# driver2REV1.net
KiCad netlist of a schematic drawn in EAGLE
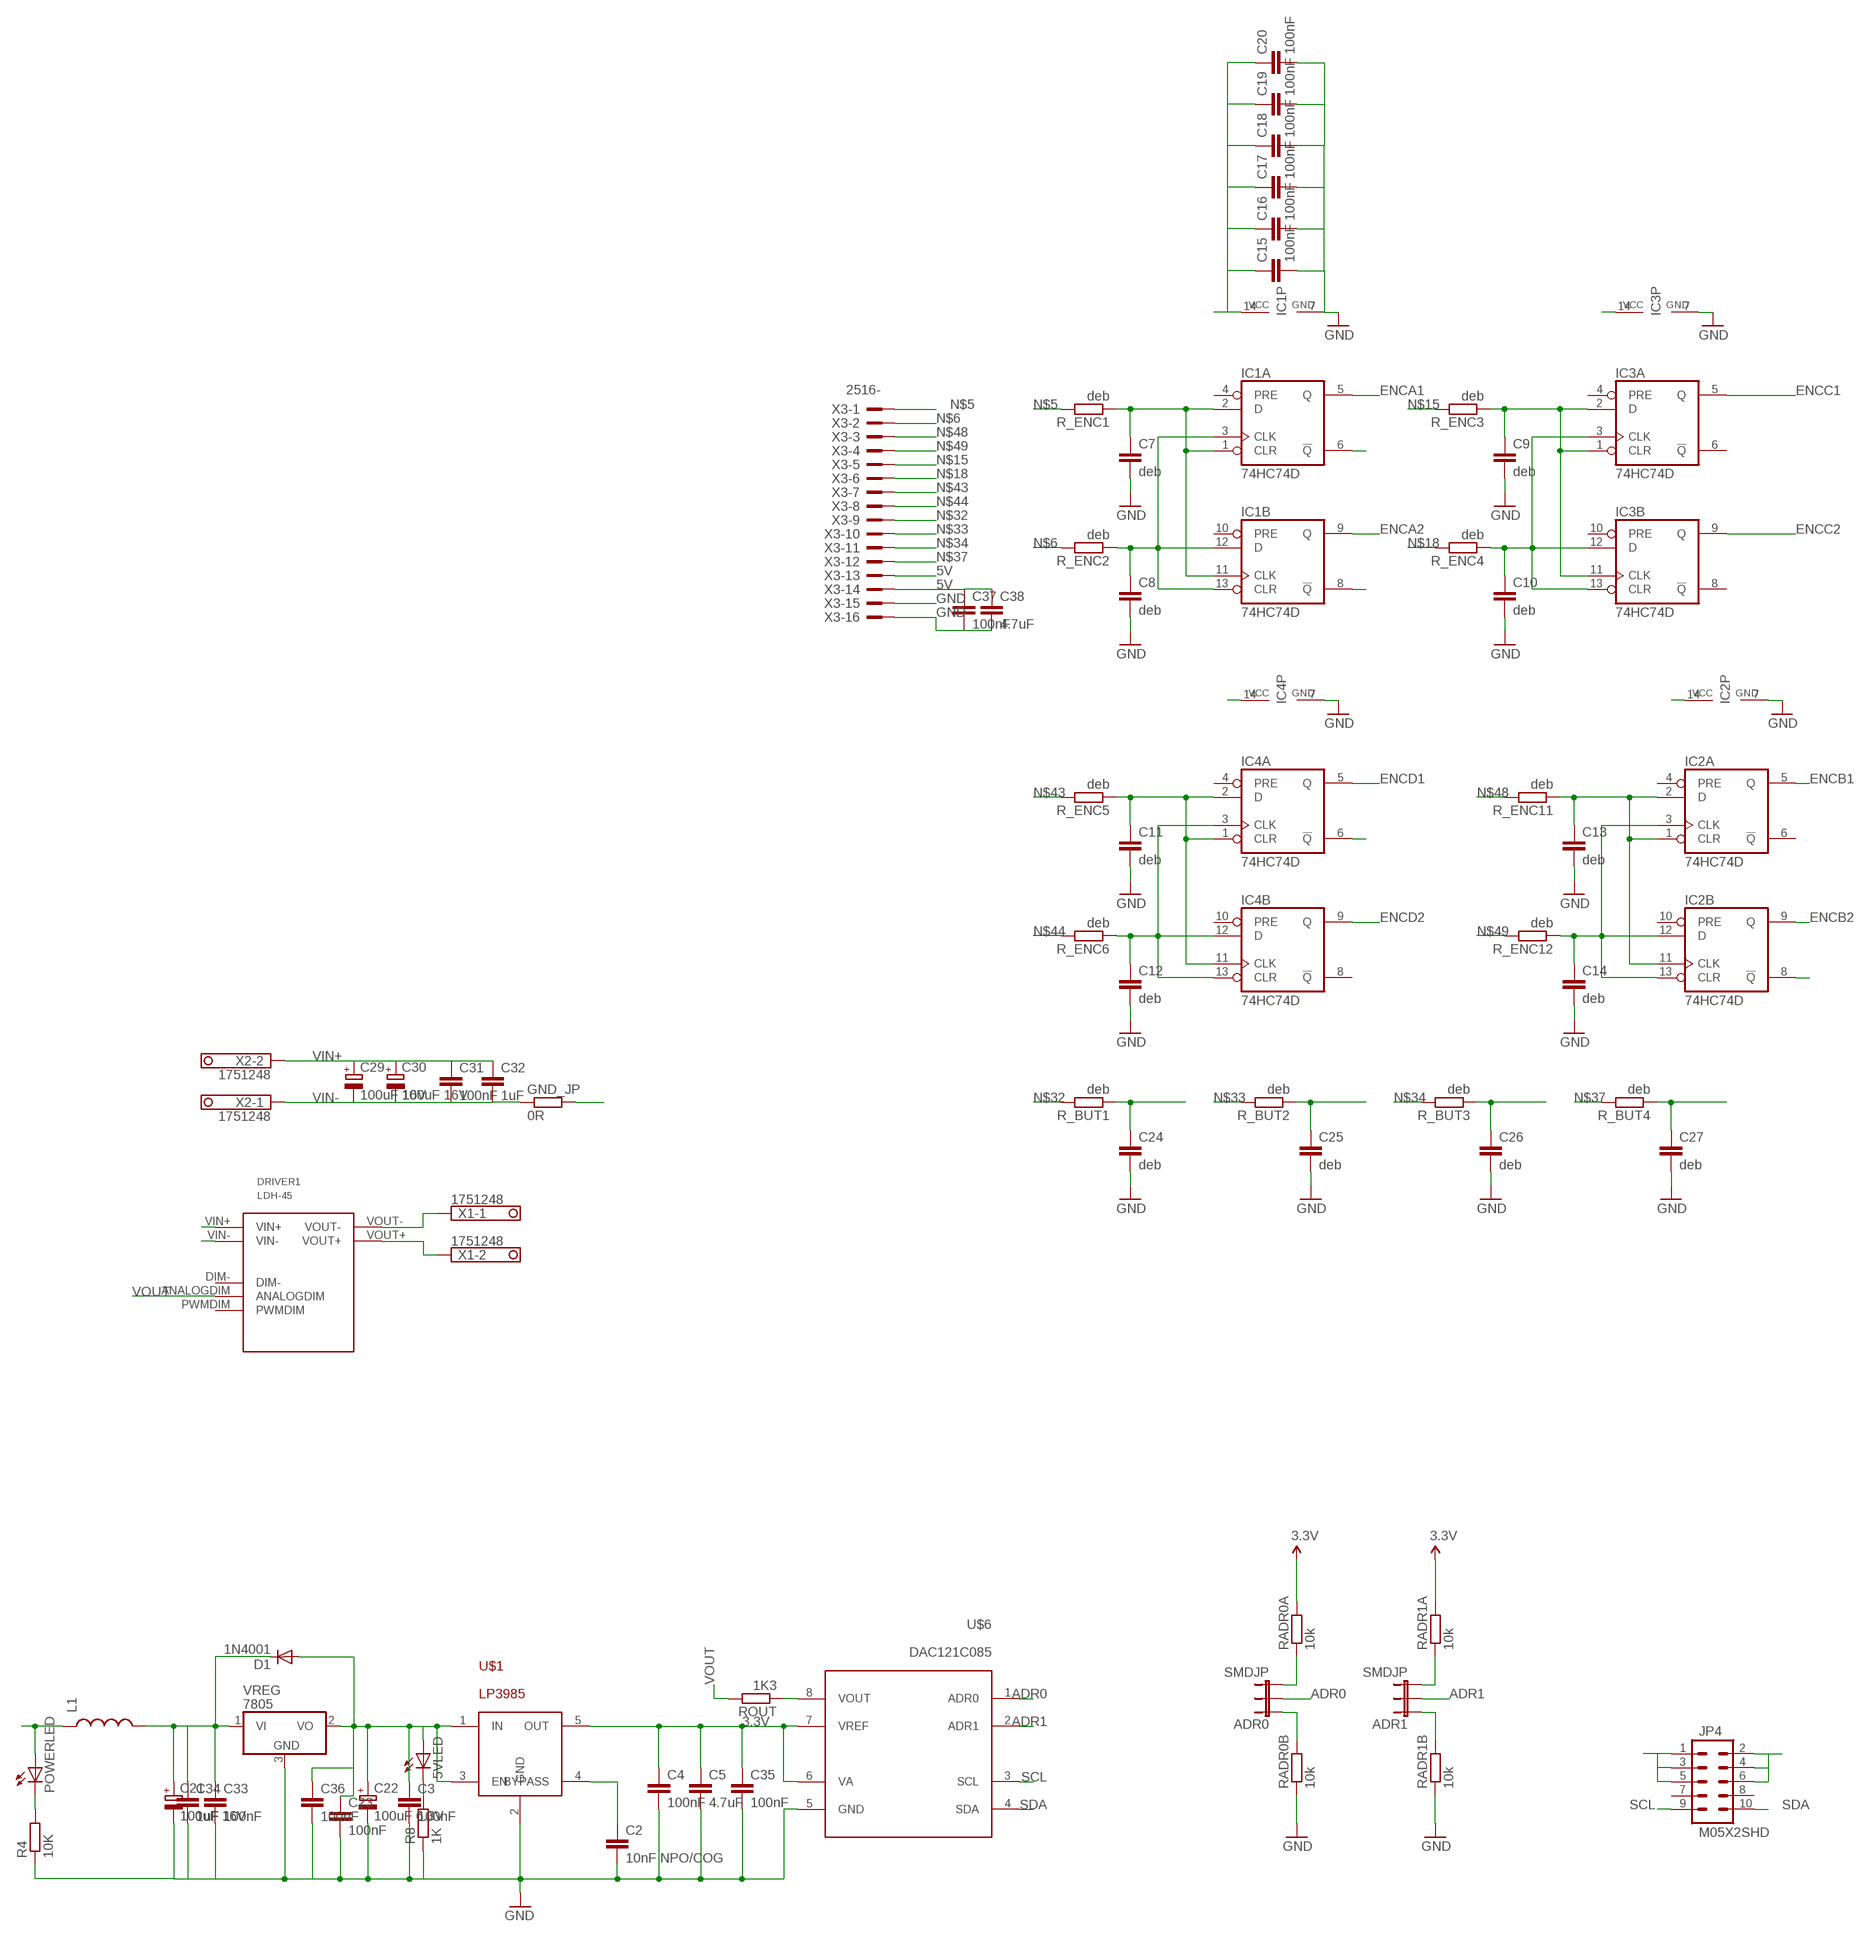
[diagram p0: schematic, sheet 1]
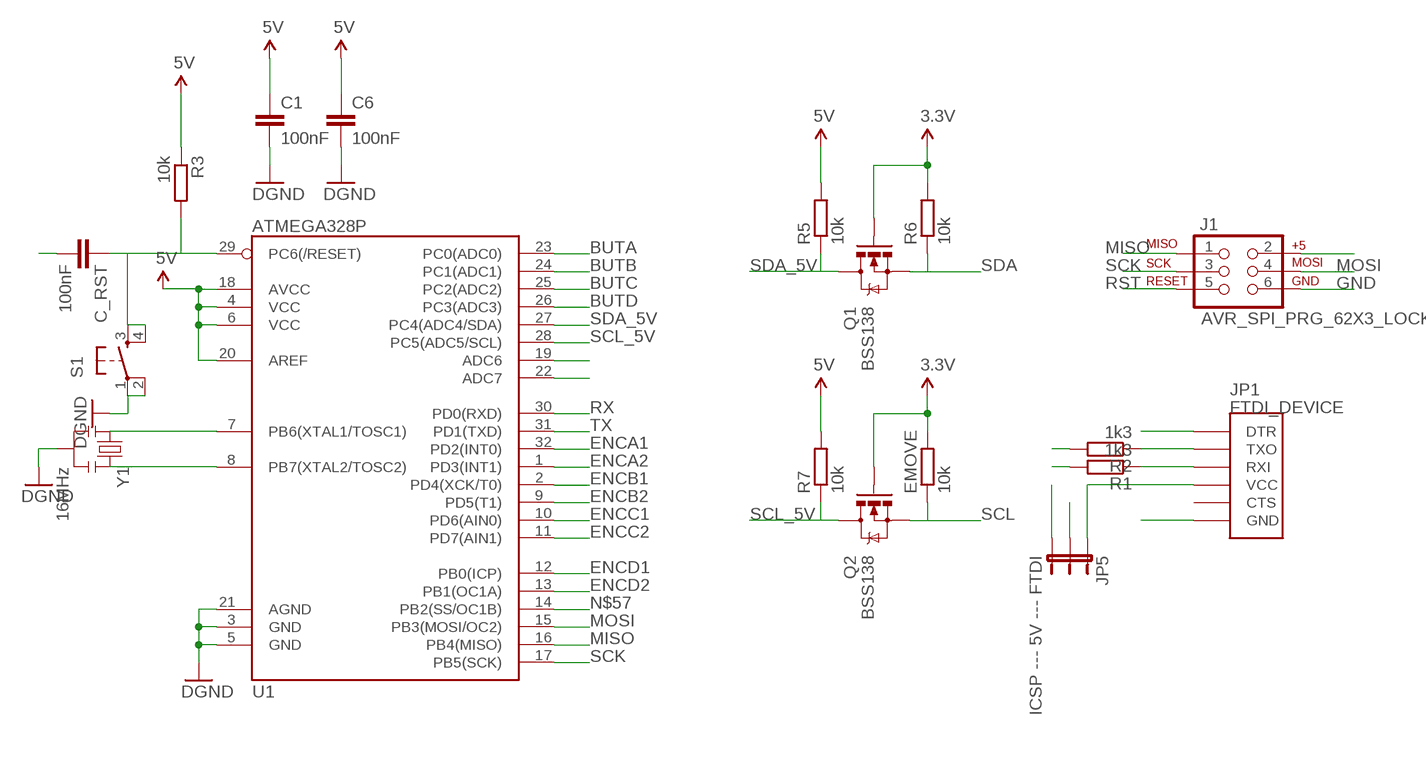
[diagram p1: schematic, sheet 2]

(export (version "E")
  (design (tool "Eeschema 10.0.6"))
  (components
    (comp (ref "5VLED")
      (value "LEDCHIP-LED0805")
      (footprint "eagle-import:CHIP-LED0805")
      (libsource (lib "eagle-import") (part "LEDCHIP-LED0805"))
    )
    (comp (ref "ADR0")
      (value "SMDJP")
      (footprint "eagle-import:SJ_3")
      (libsource (lib "eagle-import") (part "JUMPER-3-OLDSMD"))
    )
    (comp (ref "ADR1")
      (value "SMDJP")
      (footprint "eagle-import:SJ_3")
      (libsource (lib "eagle-import") (part "JUMPER-3-OLDSMD"))
    )
    (comp (ref "C2")
      (value "10nF NPO/COG")
      (footprint "eagle-import:C0805")
      (libsource (lib "eagle-import") (part "C-EUC0805"))
    )
    (comp (ref "C3")
      (value "100nF")
      (footprint "eagle-import:C0805")
      (libsource (lib "eagle-import") (part "C-EUC0805"))
    )
    (comp (ref "C4")
      (value "100nF")
      (footprint "eagle-import:C0805")
      (libsource (lib "eagle-import") (part "C-EUC0805"))
    )
    (comp (ref "C5")
      (value "4.7uF")
      (footprint "eagle-import:C0805")
      (libsource (lib "eagle-import") (part "C-EUC0805"))
    )
    (comp (ref "C7")
      (value "deb")
      (footprint "eagle-import:C0805")
      (libsource (lib "eagle-import") (part "C-EUC0805"))
    )
    (comp (ref "C8")
      (value "deb")
      (footprint "eagle-import:C0805")
      (libsource (lib "eagle-import") (part "C-EUC0805"))
    )
    (comp (ref "C9")
      (value "deb")
      (footprint "eagle-import:C0805")
      (libsource (lib "eagle-import") (part "C-EUC0805"))
    )
    (comp (ref "C10")
      (value "deb")
      (footprint "eagle-import:C0805")
      (libsource (lib "eagle-import") (part "C-EUC0805"))
    )
    (comp (ref "C11")
      (value "deb")
      (footprint "eagle-import:C0805")
      (libsource (lib "eagle-import") (part "C-EUC0805"))
    )
    (comp (ref "C12")
      (value "deb")
      (footprint "eagle-import:C0805")
      (libsource (lib "eagle-import") (part "C-EUC0805"))
    )
    (comp (ref "C13")
      (value "deb")
      (footprint "eagle-import:C0805")
      (libsource (lib "eagle-import") (part "C-EUC0805"))
    )
    (comp (ref "C14")
      (value "deb")
      (footprint "eagle-import:C0805")
      (libsource (lib "eagle-import") (part "C-EUC0805"))
    )
    (comp (ref "C15")
      (value "100nF")
      (footprint "eagle-import:C0805")
      (libsource (lib "eagle-import") (part "C-EUC0805"))
    )
    (comp (ref "C16")
      (value "100nF")
      (footprint "eagle-import:C0805")
      (libsource (lib "eagle-import") (part "C-EUC0805"))
    )
    (comp (ref "C17")
      (value "100nF")
      (footprint "eagle-import:C0805")
      (libsource (lib "eagle-import") (part "C-EUC0805"))
    )
    (comp (ref "C18")
      (value "100nF")
      (footprint "eagle-import:C0805")
      (libsource (lib "eagle-import") (part "C-EUC0805"))
    )
    (comp (ref "C19")
      (value "100nF")
      (footprint "eagle-import:C0805")
      (libsource (lib "eagle-import") (part "C-EUC0805"))
    )
    (comp (ref "C20")
      (value "100nF")
      (footprint "eagle-import:C0805")
      (libsource (lib "eagle-import") (part "C-EUC0805"))
    )
    (comp (ref "C21")
      (value "100uF 16V")
      (footprint "eagle-import:UD-6,3X5,8_NICHICON")
      (libsource (lib "eagle-import") (part "CPOL-EUUD-6,3X8,8"))
    )
    (comp (ref "C22")
      (value "100uF 6.3V")
      (footprint "eagle-import:UD-6,3X5,8_NICHICON")
      (libsource (lib "eagle-import") (part "CPOL-EUUD-6,3X8,8"))
    )
    (comp (ref "C23")
      (value "100nF")
      (footprint "eagle-import:C0805")
      (libsource (lib "eagle-import") (part "C-EUC0805"))
    )
    (comp (ref "C24")
      (value "deb")
      (footprint "eagle-import:C0805")
      (libsource (lib "eagle-import") (part "C-EUC0805"))
    )
    (comp (ref "C25")
      (value "deb")
      (footprint "eagle-import:C0805")
      (libsource (lib "eagle-import") (part "C-EUC0805"))
    )
    (comp (ref "C26")
      (value "deb")
      (footprint "eagle-import:C0805")
      (libsource (lib "eagle-import") (part "C-EUC0805"))
    )
    (comp (ref "C27")
      (value "deb")
      (footprint "eagle-import:C0805")
      (libsource (lib "eagle-import") (part "C-EUC0805"))
    )
    (comp (ref "C29")
      (value "100uF 16V")
      (footprint "eagle-import:UD-6,3X5,8_NICHICON")
      (libsource (lib "eagle-import") (part "CPOL-EUUD-6,3X8,8"))
    )
    (comp (ref "C30")
      (value "100uF 16V")
      (footprint "eagle-import:UD-6,3X5,8_NICHICON")
      (libsource (lib "eagle-import") (part "CPOL-EUUD-6,3X8,8"))
    )
    (comp (ref "C31")
      (value "100nF")
      (footprint "eagle-import:C0805")
      (libsource (lib "eagle-import") (part "C-EUC0805"))
    )
    (comp (ref "C32")
      (value "1uF")
      (footprint "eagle-import:C0805")
      (libsource (lib "eagle-import") (part "C-EUC0805"))
    )
    (comp (ref "C33")
      (value "100nF")
      (footprint "eagle-import:C0805")
      (libsource (lib "eagle-import") (part "C-EUC0805"))
    )
    (comp (ref "C34")
      (value "1uF")
      (footprint "eagle-import:C0805")
      (libsource (lib "eagle-import") (part "C-EUC0805"))
    )
    (comp (ref "C35")
      (value "100nF")
      (footprint "eagle-import:C0805")
      (libsource (lib "eagle-import") (part "C-EUC0805"))
    )
    (comp (ref "C36")
      (value "100nF")
      (footprint "eagle-import:C0805")
      (libsource (lib "eagle-import") (part "C-EUC0805"))
    )
    (comp (ref "C37")
      (value "100nF")
      (footprint "eagle-import:C0805")
      (libsource (lib "eagle-import") (part "C-EUC0805"))
    )
    (comp (ref "C38")
      (value "4.7uF")
      (footprint "eagle-import:C0805")
      (libsource (lib "eagle-import") (part "C-EUC0805"))
    )
    (comp (ref "D1")
      (value "1N4001")
      (footprint "eagle-import:SMB-DIODE")
      (libsource (lib "eagle-import") (part "DIODESMB"))
    )
    (comp (ref "DRIVER1")
      (value "LDH-45")
      (footprint "eagle-import:LDH-45")
      (libsource (lib "eagle-import") (part "LDH-45"))
    )
    (comp (ref "GND_JP")
      (value "0R")
      (footprint "eagle-import:R1210")
      (libsource (lib "eagle-import") (part "R-EU_R1210"))
    )
    (comp (ref "IC1")
      (value "74HC74D")
      (footprint "eagle-import:SO14")
      (libsource (lib "eagle-import") (part "7474DHC"))
    )
    (comp (ref "IC2")
      (value "74HC74D")
      (footprint "eagle-import:SO14")
      (libsource (lib "eagle-import") (part "7474DHC"))
    )
    (comp (ref "IC3")
      (value "74HC74D")
      (footprint "eagle-import:SO14")
      (libsource (lib "eagle-import") (part "7474DHC"))
    )
    (comp (ref "IC4")
      (value "74HC74D")
      (footprint "eagle-import:SO14")
      (libsource (lib "eagle-import") (part "7474DHC"))
    )
    (comp (ref "JP4")
      (value "M05X2SHD")
      (footprint "eagle-import:2X5-SHROUDED")
      (libsource (lib "eagle-import") (part "M05X2SHD"))
    )
    (comp (ref "L1")
      (value "INDUCTOR0805")
      (footprint "eagle-import:0805")
      (libsource (lib "eagle-import") (part "INDUCTOR0805"))
    )
    (comp (ref "POWERLED")
      (value "LEDCHIP-LED0805")
      (footprint "eagle-import:CHIP-LED0805")
      (libsource (lib "eagle-import") (part "LEDCHIP-LED0805"))
    )
    (comp (ref "R4")
      (value "10K")
      (footprint "eagle-import:R0805")
      (libsource (lib "eagle-import") (part "wes_R-EU_R0805"))
    )
    (comp (ref "R8")
      (value "1K")
      (footprint "eagle-import:R0805")
      (libsource (lib "eagle-import") (part "wes_R-EU_R0805"))
    )
    (comp (ref "RADR0A")
      (value "10k")
      (footprint "eagle-import:R0603")
      (libsource (lib "eagle-import") (part "wes_R-EU_R0603"))
    )
    (comp (ref "RADR0B")
      (value "10k")
      (footprint "eagle-import:R0603")
      (libsource (lib "eagle-import") (part "wes_R-EU_R0603"))
    )
    (comp (ref "RADR1A")
      (value "10k")
      (footprint "eagle-import:R0603")
      (libsource (lib "eagle-import") (part "wes_R-EU_R0603"))
    )
    (comp (ref "RADR1B")
      (value "10k")
      (footprint "eagle-import:R0603")
      (libsource (lib "eagle-import") (part "wes_R-EU_R0603"))
    )
    (comp (ref "ROUT")
      (value "1K3")
      (footprint "eagle-import:R0603")
      (libsource (lib "eagle-import") (part "wes_R-EU_R0603"))
    )
    (comp (ref "R_BUT1")
      (value "deb")
      (footprint "eagle-import:R0603")
      (libsource (lib "eagle-import") (part "wes_R-EU_R0603"))
    )
    (comp (ref "R_BUT2")
      (value "deb")
      (footprint "eagle-import:R0603")
      (libsource (lib "eagle-import") (part "wes_R-EU_R0603"))
    )
    (comp (ref "R_BUT3")
      (value "deb")
      (footprint "eagle-import:R0603")
      (libsource (lib "eagle-import") (part "wes_R-EU_R0603"))
    )
    (comp (ref "R_BUT4")
      (value "deb")
      (footprint "eagle-import:R0603")
      (libsource (lib "eagle-import") (part "wes_R-EU_R0603"))
    )
    (comp (ref "R_ENC1")
      (value "deb")
      (footprint "eagle-import:R0603")
      (libsource (lib "eagle-import") (part "wes_R-EU_R0603"))
    )
    (comp (ref "R_ENC2")
      (value "deb")
      (footprint "eagle-import:R0603")
      (libsource (lib "eagle-import") (part "wes_R-EU_R0603"))
    )
    (comp (ref "R_ENC3")
      (value "deb")
      (footprint "eagle-import:R0603")
      (libsource (lib "eagle-import") (part "wes_R-EU_R0603"))
    )
    (comp (ref "R_ENC4")
      (value "deb")
      (footprint "eagle-import:R0603")
      (libsource (lib "eagle-import") (part "wes_R-EU_R0603"))
    )
    (comp (ref "R_ENC5")
      (value "deb")
      (footprint "eagle-import:R0603")
      (libsource (lib "eagle-import") (part "wes_R-EU_R0603"))
    )
    (comp (ref "R_ENC6")
      (value "deb")
      (footprint "eagle-import:R0603")
      (libsource (lib "eagle-import") (part "wes_R-EU_R0603"))
    )
    (comp (ref "R_ENC11")
      (value "deb")
      (footprint "eagle-import:R0603")
      (libsource (lib "eagle-import") (part "wes_R-EU_R0603"))
    )
    (comp (ref "R_ENC12")
      (value "deb")
      (footprint "eagle-import:R0603")
      (libsource (lib "eagle-import") (part "wes_R-EU_R0603"))
    )
    (comp (ref "U$1")
      (value "LP3985")
      (footprint "eagle-import:SOT23-5")
      (libsource (lib "eagle-import") (part "LP3985"))
    )
    (comp (ref "U$6")
      (value "DAC121C085")
      (footprint "eagle-import:VSSOP-8")
      (libsource (lib "eagle-import") (part "DAC121C085"))
    )
    (comp (ref "VREG")
      (value "7805")
      (footprint "eagle-import:TO252")
      (libsource (lib "eagle-import") (part "78DT05"))
    )
    (comp (ref "X1")
      (value "1751248")
      (footprint "eagle-import:1751248")
      (libsource (lib "eagle-import") (part "1751248"))
    )
    (comp (ref "X2")
      (value "1751248")
      (footprint "eagle-import:1751248")
      (fields (field (name "OC_FARNELL") "unknown") (field (name "OC_NEWARK") "unknown"))
      (libsource (lib "eagle-import") (part "1751248"))
    )
    (comp (ref "X3")
      (value "2516-")
      (footprint "eagle-import:PAK100_2500-16")
      (libsource (lib "eagle-import") (part "2516-"))
    )
    (comp (ref "C1")
      (value "100nF")
      (footprint "eagle-import:C0805")
      (libsource (lib "eagle-import") (part "C-EUC0805"))
    )
    (comp (ref "C6")
      (value "100nF")
      (footprint "eagle-import:C0805")
      (libsource (lib "eagle-import") (part "C-EUC0805"))
    )
    (comp (ref "C_RST")
      (value "100nF")
      (footprint "eagle-import:C0805")
      (libsource (lib "eagle-import") (part "C-EUC0805"))
    )
    (comp (ref "EMOVE")
      (value "10k")
      (footprint "eagle-import:R0603")
      (libsource (lib "eagle-import") (part "wes_R-EU_R0603"))
    )
    (comp (ref "J1")
      (value "AVR_SPI_PRG_62X3_LOCK")
      (footprint "eagle-import:2X3_LOCK")
      (libsource (lib "eagle-import") (part "AVR_SPI_PRG_62X3_LOCK"))
    )
    (comp (ref "JP1")
      (value "FTDI_DEVICE")
      (footprint "eagle-import:FTDI_DEVICE_SIDE")
      (libsource (lib "eagle-import") (part "FTDI_DEVICE"))
    )
    (comp (ref "JP5")
      (value "ICSP --- 5V --- FTDI")
      (footprint "eagle-import:SJ_3")
      (libsource (lib "eagle-import") (part "JUMPER-3SMD"))
    )
    (comp (ref "Q1")
      (value "BSS138")
      (footprint "eagle-import:SOT23")
      (libsource (lib "eagle-import") (part "MOSFET-NCHANNELBSS138"))
    )
    (comp (ref "Q2")
      (value "BSS138")
      (footprint "eagle-import:SOT23")
      (libsource (lib "eagle-import") (part "MOSFET-NCHANNELBSS138"))
    )
    (comp (ref "R1")
      (value "1k3")
      (footprint "eagle-import:R0603")
      (libsource (lib "eagle-import") (part "wes_R-EU_R0603"))
    )
    (comp (ref "R2")
      (value "1k3")
      (footprint "eagle-import:R0603")
      (libsource (lib "eagle-import") (part "wes_R-EU_R0603"))
    )
    (comp (ref "R3")
      (value "10k")
      (footprint "eagle-import:R0603")
      (libsource (lib "eagle-import") (part "wes_R-EU_R0603"))
    )
    (comp (ref "R5")
      (value "10k")
      (footprint "eagle-import:R0603")
      (libsource (lib "eagle-import") (part "wes_R-EU_R0603"))
    )
    (comp (ref "R6")
      (value "10k")
      (footprint "eagle-import:R0603")
      (libsource (lib "eagle-import") (part "wes_R-EU_R0603"))
    )
    (comp (ref "R7")
      (value "10k")
      (footprint "eagle-import:R0603")
      (libsource (lib "eagle-import") (part "wes_R-EU_R0603"))
    )
    (comp (ref "S1")
      (value "TAC_SWITCHSMD")
      (footprint "eagle-import:TACTILE_SWITCH_SMD")
      (libsource (lib "eagle-import") (part "TAC_SWITCHSMD"))
    )
    (comp (ref "U1")
      (value "ATMEGA328P")
      (footprint "eagle-import:TQFP32-08")
      (libsource (lib "eagle-import") (part "ATMEGA328_SMT"))
    )
    (comp (ref "Y1")
      (value "16MHz")
      (footprint "eagle-import:RESONATOR-SMD")
      (libsource (lib "eagle-import") (part "RESONATOR8MHZ"))
    )
  )
  (nets
    (net (code "1") (name "3.3V") (class "Default")
      (node (ref "C35") (pin "1") (pinfunction "1_1") (pintype "passive"))
      (node (ref "C4") (pin "1") (pinfunction "1_1") (pintype "passive"))
      (node (ref "C5") (pin "1") (pinfunction "1_1") (pintype "passive"))
      (node (ref "EMOVE") (pin "2") (pinfunction "2_2") (pintype "passive"))
      (node (ref "Q1") (pin "1") (pinfunction "G_1") (pintype "passive"))
      (node (ref "Q2") (pin "1") (pinfunction "G_1") (pintype "passive"))
      (node (ref "R6") (pin "2") (pinfunction "2_2") (pintype "passive"))
      (node (ref "RADR0A") (pin "2") (pinfunction "2_2") (pintype "passive"))
      (node (ref "RADR1A") (pin "2") (pinfunction "2_2") (pintype "passive"))
      (node (ref "U$1") (pin "5") (pinfunction "OUT_5") (pintype "bidirectional"))
      (node (ref "U$6") (pin "6") (pinfunction "VA_6") (pintype "bidirectional"))
      (node (ref "U$6") (pin "7") (pinfunction "VREF_7") (pintype "bidirectional"))
    )
    (net (code "2") (name "5V") (class "Default")
      (node (ref "5VLED") (pin "A") (pinfunction "A_A") (pintype "passive"))
      (node (ref "C1") (pin "1") (pinfunction "1_1") (pintype "passive"))
      (node (ref "C15") (pin "1") (pinfunction "1_1") (pintype "passive"))
      (node (ref "C16") (pin "1") (pinfunction "1_1") (pintype "passive"))
      (node (ref "C17") (pin "1") (pinfunction "1_1") (pintype "passive"))
      (node (ref "C18") (pin "1") (pinfunction "1_1") (pintype "passive"))
      (node (ref "C19") (pin "1") (pinfunction "1_1") (pintype "passive"))
      (node (ref "C20") (pin "1") (pinfunction "1_1") (pintype "passive"))
      (node (ref "C22") (pin "+") (pinfunction "+_+") (pintype "passive"))
      (node (ref "C23") (pin "1") (pinfunction "1_1") (pintype "passive"))
      (node (ref "C3") (pin "1") (pinfunction "1_1") (pintype "passive"))
      (node (ref "C36") (pin "1") (pinfunction "1_1") (pintype "passive"))
      (node (ref "C37") (pin "1") (pinfunction "1_1") (pintype "passive"))
      (node (ref "C38") (pin "1") (pinfunction "1_1") (pintype "passive"))
      (node (ref "C6") (pin "1") (pinfunction "1_1") (pintype "passive"))
      (node (ref "D1") (pin "A") (pinfunction "A_A") (pintype "passive"))
      (node (ref "IC1") (pin "14") (pinfunction "VCC_14") (pintype "power_in"))
      (node (ref "IC2") (pin "14") (pinfunction "VCC_14") (pintype "power_in"))
      (node (ref "IC3") (pin "14") (pinfunction "VCC_14") (pintype "power_in"))
      (node (ref "IC4") (pin "14") (pinfunction "VCC_14") (pintype "power_in"))
      (node (ref "JP4") (pin "2") (pinfunction "2_2") (pintype "passive"))
      (node (ref "JP4") (pin "4") (pinfunction "4_4") (pintype "passive"))
      (node (ref "JP4") (pin "6") (pinfunction "6_6") (pintype "passive"))
      (node (ref "JP5") (pin "2") (pinfunction "2_2") (pintype "passive"))
      (node (ref "R3") (pin "1") (pinfunction "1_1") (pintype "passive"))
      (node (ref "R5") (pin "2") (pinfunction "2_2") (pintype "passive"))
      (node (ref "R7") (pin "2") (pinfunction "2_2") (pintype "passive"))
      (node (ref "U$1") (pin "1") (pinfunction "IN_1") (pintype "bidirectional"))
      (node (ref "U$1") (pin "3") (pinfunction "EN_3") (pintype "bidirectional"))
      (node (ref "U1") (pin "18") (pinfunction "AVCC_18") (pintype "bidirectional"))
      (node (ref "U1") (pin "20") (pinfunction "AREF_20") (pintype "bidirectional"))
      (node (ref "U1") (pin "4") (pinfunction "VCC_4") (pintype "bidirectional"))
      (node (ref "U1") (pin "6") (pinfunction "VCC_6") (pintype "bidirectional"))
      (node (ref "VREG") (pin "2") (pinfunction "VO_2") (pintype "passive"))
      (node (ref "X3") (pin "13") (pinfunction "KL_13") (pintype "passive"))
      (node (ref "X3") (pin "14") (pinfunction "KL_14") (pintype "passive"))
    )
    (net (code "3") (name "ADR0") (class "Default")
      (node (ref "ADR0") (pin "2") (pinfunction "2_2") (pintype "passive"))
      (node (ref "U$6") (pin "1") (pinfunction "ADR0_1") (pintype "bidirectional"))
    )
    (net (code "4") (name "ADR1") (class "Default")
      (node (ref "ADR1") (pin "2") (pinfunction "2_2") (pintype "passive"))
      (node (ref "U$6") (pin "2") (pinfunction "ADR1_2") (pintype "bidirectional"))
    )
    (net (code "5") (name "BUTA") (class "Default")
      (node (ref "C24") (pin "1") (pinfunction "1_1") (pintype "passive"))
      (node (ref "R_BUT1") (pin "1") (pinfunction "1_1") (pintype "passive"))
      (node (ref "U1") (pin "23") (pinfunction "PC0(ADC0)_23") (pintype "bidirectional"))
    )
    (net (code "6") (name "BUTB") (class "Default")
      (node (ref "C25") (pin "1") (pinfunction "1_1") (pintype "passive"))
      (node (ref "R_BUT2") (pin "1") (pinfunction "1_1") (pintype "passive"))
      (node (ref "U1") (pin "24") (pinfunction "PC1(ADC1)_24") (pintype "bidirectional"))
    )
    (net (code "7") (name "BUTC") (class "Default")
      (node (ref "C26") (pin "1") (pinfunction "1_1") (pintype "passive"))
      (node (ref "R_BUT3") (pin "1") (pinfunction "1_1") (pintype "passive"))
      (node (ref "U1") (pin "25") (pinfunction "PC2(ADC2)_25") (pintype "bidirectional"))
    )
    (net (code "8") (name "BUTD") (class "Default")
      (node (ref "C27") (pin "1") (pinfunction "1_1") (pintype "passive"))
      (node (ref "R_BUT4") (pin "1") (pinfunction "1_1") (pintype "passive"))
      (node (ref "U1") (pin "26") (pinfunction "PC3(ADC3)_26") (pintype "bidirectional"))
    )
    (net (code "9") (name "ENCA1") (class "Default")
      (node (ref "IC1") (pin "5") (pinfunction "Q_5") (pintype "output"))
      (node (ref "U1") (pin "32") (pinfunction "PD2(INT0)_32") (pintype "bidirectional"))
    )
    (net (code "10") (name "ENCA2") (class "Default")
      (node (ref "IC1") (pin "9") (pinfunction "Q_9") (pintype "output"))
      (node (ref "U1") (pin "1") (pinfunction "PD3(INT1)_1") (pintype "bidirectional"))
    )
    (net (code "11") (name "ENCB1") (class "Default")
      (node (ref "IC2") (pin "5") (pinfunction "Q_5") (pintype "output"))
      (node (ref "U1") (pin "2") (pinfunction "PD4(XCK/T0)_2") (pintype "bidirectional"))
    )
    (net (code "12") (name "ENCB2") (class "Default")
      (node (ref "IC2") (pin "9") (pinfunction "Q_9") (pintype "output"))
      (node (ref "U1") (pin "9") (pinfunction "PD5(T1)_9") (pintype "bidirectional"))
    )
    (net (code "13") (name "ENCC1") (class "Default")
      (node (ref "IC3") (pin "5") (pinfunction "Q_5") (pintype "output"))
      (node (ref "U1") (pin "10") (pinfunction "PD6(AIN0)_10") (pintype "bidirectional"))
    )
    (net (code "14") (name "ENCC2") (class "Default")
      (node (ref "IC3") (pin "9") (pinfunction "Q_9") (pintype "output"))
      (node (ref "U1") (pin "11") (pinfunction "PD7(AIN1)_11") (pintype "bidirectional"))
    )
    (net (code "15") (name "ENCD1") (class "Default")
      (node (ref "IC4") (pin "5") (pinfunction "Q_5") (pintype "output"))
      (node (ref "U1") (pin "12") (pinfunction "PB0(ICP)_12") (pintype "bidirectional"))
    )
    (net (code "16") (name "ENCD2") (class "Default")
      (node (ref "IC4") (pin "9") (pinfunction "Q_9") (pintype "output"))
      (node (ref "U1") (pin "13") (pinfunction "PB1(OC1A)_13") (pintype "bidirectional"))
    )
    (net (code "17") (name "FTDI_RST") (class "Default")
      (node (ref "C_RST") (pin "2") (pinfunction "2_2") (pintype "passive"))
      (node (ref "JP1") (pin "P$1") (pinfunction "DTR_P$1") (pintype "bidirectional"))
    )
    (net (code "18") (name "GND") (class "Default")
      (node (ref "C1") (pin "2") (pinfunction "2_2") (pintype "passive"))
      (node (ref "C10") (pin "2") (pinfunction "2_2") (pintype "passive"))
      (node (ref "C11") (pin "2") (pinfunction "2_2") (pintype "passive"))
      (node (ref "C12") (pin "2") (pinfunction "2_2") (pintype "passive"))
      (node (ref "C13") (pin "2") (pinfunction "2_2") (pintype "passive"))
      (node (ref "C14") (pin "2") (pinfunction "2_2") (pintype "passive"))
      (node (ref "C15") (pin "2") (pinfunction "2_2") (pintype "passive"))
      (node (ref "C16") (pin "2") (pinfunction "2_2") (pintype "passive"))
      (node (ref "C17") (pin "2") (pinfunction "2_2") (pintype "passive"))
      (node (ref "C18") (pin "2") (pinfunction "2_2") (pintype "passive"))
      (node (ref "C19") (pin "2") (pinfunction "2_2") (pintype "passive"))
      (node (ref "C2") (pin "2") (pinfunction "2_2") (pintype "passive"))
      (node (ref "C20") (pin "2") (pinfunction "2_2") (pintype "passive"))
      (node (ref "C21") (pin "-") (pinfunction "-_-") (pintype "passive"))
      (node (ref "C22") (pin "-") (pinfunction "-_-") (pintype "passive"))
      (node (ref "C23") (pin "2") (pinfunction "2_2") (pintype "passive"))
      (node (ref "C24") (pin "2") (pinfunction "2_2") (pintype "passive"))
      (node (ref "C25") (pin "2") (pinfunction "2_2") (pintype "passive"))
      (node (ref "C26") (pin "2") (pinfunction "2_2") (pintype "passive"))
      (node (ref "C27") (pin "2") (pinfunction "2_2") (pintype "passive"))
      (node (ref "C3") (pin "2") (pinfunction "2_2") (pintype "passive"))
      (node (ref "C33") (pin "2") (pinfunction "2_2") (pintype "passive"))
      (node (ref "C34") (pin "2") (pinfunction "2_2") (pintype "passive"))
      (node (ref "C35") (pin "2") (pinfunction "2_2") (pintype "passive"))
      (node (ref "C36") (pin "2") (pinfunction "2_2") (pintype "passive"))
      (node (ref "C37") (pin "2") (pinfunction "2_2") (pintype "passive"))
      (node (ref "C38") (pin "2") (pinfunction "2_2") (pintype "passive"))
      (node (ref "C4") (pin "2") (pinfunction "2_2") (pintype "passive"))
      (node (ref "C5") (pin "2") (pinfunction "2_2") (pintype "passive"))
      (node (ref "C6") (pin "2") (pinfunction "2_2") (pintype "passive"))
      (node (ref "C7") (pin "2") (pinfunction "2_2") (pintype "passive"))
      (node (ref "C8") (pin "2") (pinfunction "2_2") (pintype "passive"))
      (node (ref "C9") (pin "2") (pinfunction "2_2") (pintype "passive"))
      (node (ref "GND_JP") (pin "2") (pinfunction "2_2") (pintype "passive"))
      (node (ref "IC1") (pin "7") (pinfunction "GND_7") (pintype "power_in"))
      (node (ref "IC2") (pin "7") (pinfunction "GND_7") (pintype "power_in"))
      (node (ref "IC3") (pin "7") (pinfunction "GND_7") (pintype "power_in"))
      (node (ref "IC4") (pin "7") (pinfunction "GND_7") (pintype "power_in"))
      (node (ref "J1") (pin "6") (pinfunction "6_6") (pintype "passive"))
      (node (ref "JP1") (pin "P$6") (pinfunction "GND_P$6") (pintype "bidirectional"))
      (node (ref "JP4") (pin "1") (pinfunction "1_1") (pintype "passive"))
      (node (ref "JP4") (pin "3") (pinfunction "3_3") (pintype "passive"))
      (node (ref "JP4") (pin "5") (pinfunction "5_5") (pintype "passive"))
      (node (ref "R4") (pin "1") (pinfunction "1_1") (pintype "passive"))
      (node (ref "R8") (pin "1") (pinfunction "1_1") (pintype "passive"))
      (node (ref "RADR0B") (pin "1") (pinfunction "1_1") (pintype "passive"))
      (node (ref "RADR1B") (pin "1") (pinfunction "1_1") (pintype "passive"))
      (node (ref "S1") (pin "1") (pinfunction "1_1") (pintype "passive"))
      (node (ref "S1") (pin "2") (pinfunction "2_2") (pintype "passive"))
      (node (ref "U$1") (pin "2") (pinfunction "GND_2") (pintype "bidirectional"))
      (node (ref "U$6") (pin "5") (pinfunction "GND_5") (pintype "bidirectional"))
      (node (ref "U1") (pin "21") (pinfunction "AGND_21") (pintype "bidirectional"))
      (node (ref "U1") (pin "3") (pinfunction "GND_3") (pintype "bidirectional"))
      (node (ref "U1") (pin "5") (pinfunction "GND_5") (pintype "bidirectional"))
      (node (ref "VREG") (pin "3") (pinfunction "GND_3") (pintype "passive"))
      (node (ref "X3") (pin "15") (pinfunction "KL_15") (pintype "passive"))
      (node (ref "X3") (pin "16") (pinfunction "KL_16") (pintype "passive"))
      (node (ref "Y1") (pin "2") (pinfunction "2_2") (pintype "passive"))
    )
    (net (code "19") (name "ISP_5V") (class "Default")
      (node (ref "J1") (pin "2") (pinfunction "2_2") (pintype "passive"))
      (node (ref "JP5") (pin "3") (pinfunction "3_3") (pintype "passive"))
    )
    (net (code "20") (name "MISO") (class "Default")
      (node (ref "J1") (pin "1") (pinfunction "1_1") (pintype "passive"))
      (node (ref "U1") (pin "16") (pinfunction "PB4(MISO)_16") (pintype "bidirectional"))
    )
    (net (code "21") (name "MOSI") (class "Default")
      (node (ref "J1") (pin "4") (pinfunction "4_4") (pintype "passive"))
      (node (ref "U1") (pin "15") (pinfunction "PB3(MOSI/OC2)_15") (pintype "bidirectional"))
    )
    (net (code "22") (name "N$5") (class "Default")
      (node (ref "R_ENC1") (pin "2") (pinfunction "2_2") (pintype "passive"))
      (node (ref "X3") (pin "1") (pinfunction "KL_1") (pintype "passive"))
    )
    (net (code "23") (name "N$6") (class "Default")
      (node (ref "R_ENC2") (pin "2") (pinfunction "2_2") (pintype "passive"))
      (node (ref "X3") (pin "2") (pinfunction "KL_2") (pintype "passive"))
    )
    (net (code "24") (name "N$15") (class "Default")
      (node (ref "R_ENC3") (pin "2") (pinfunction "2_2") (pintype "passive"))
      (node (ref "X3") (pin "5") (pinfunction "KL_5") (pintype "passive"))
    )
    (net (code "25") (name "N$18") (class "Default")
      (node (ref "R_ENC4") (pin "2") (pinfunction "2_2") (pintype "passive"))
      (node (ref "X3") (pin "6") (pinfunction "KL_6") (pintype "passive"))
    )
    (net (code "26") (name "N$32") (class "Default")
      (node (ref "R_BUT1") (pin "2") (pinfunction "2_2") (pintype "passive"))
      (node (ref "X3") (pin "9") (pinfunction "KL_9") (pintype "passive"))
    )
    (net (code "27") (name "N$33") (class "Default")
      (node (ref "R_BUT2") (pin "2") (pinfunction "2_2") (pintype "passive"))
      (node (ref "X3") (pin "10") (pinfunction "KL_10") (pintype "passive"))
    )
    (net (code "28") (name "N$34") (class "Default")
      (node (ref "R_BUT3") (pin "2") (pinfunction "2_2") (pintype "passive"))
      (node (ref "X3") (pin "11") (pinfunction "KL_11") (pintype "passive"))
    )
    (net (code "29") (name "N$37") (class "Default")
      (node (ref "R_BUT4") (pin "2") (pinfunction "2_2") (pintype "passive"))
      (node (ref "X3") (pin "12") (pinfunction "KL_12") (pintype "passive"))
    )
    (net (code "30") (name "N$43") (class "Default")
      (node (ref "R_ENC5") (pin "2") (pinfunction "2_2") (pintype "passive"))
      (node (ref "X3") (pin "7") (pinfunction "KL_7") (pintype "passive"))
    )
    (net (code "31") (name "N$44") (class "Default")
      (node (ref "R_ENC6") (pin "2") (pinfunction "2_2") (pintype "passive"))
      (node (ref "X3") (pin "8") (pinfunction "KL_8") (pintype "passive"))
    )
    (net (code "32") (name "N$48") (class "Default")
      (node (ref "R_ENC11") (pin "2") (pinfunction "2_2") (pintype "passive"))
      (node (ref "X3") (pin "3") (pinfunction "KL_3") (pintype "passive"))
    )
    (net (code "33") (name "N$49") (class "Default")
      (node (ref "R_ENC12") (pin "2") (pinfunction "2_2") (pintype "passive"))
      (node (ref "X3") (pin "4") (pinfunction "KL_4") (pintype "passive"))
    )
    (net (code "34") (name "N$57") (class "Default")
      (node (ref "U1") (pin "14") (pinfunction "PB2(SS/OC1B)_14") (pintype "bidirectional"))
    )
    (net (code "35") (name "Net-(5VLED-PadC)") (class "Default")
      (node (ref "5VLED") (pin "C") (pinfunction "C_C") (pintype "passive"))
      (node (ref "R8") (pin "2") (pinfunction "2_2") (pintype "passive"))
    )
    (net (code "36") (name "Net-(ADR0-Pad1)") (class "Default")
      (node (ref "ADR0") (pin "1") (pinfunction "1_1") (pintype "passive"))
      (node (ref "RADR0B") (pin "2") (pinfunction "2_2") (pintype "passive"))
    )
    (net (code "37") (name "Net-(ADR0-Pad3)") (class "Default")
      (node (ref "ADR0") (pin "3") (pinfunction "3_3") (pintype "passive"))
      (node (ref "RADR0A") (pin "1") (pinfunction "1_1") (pintype "passive"))
    )
    (net (code "38") (name "Net-(ADR1-Pad1)") (class "Default")
      (node (ref "ADR1") (pin "1") (pinfunction "1_1") (pintype "passive"))
      (node (ref "RADR1B") (pin "2") (pinfunction "2_2") (pintype "passive"))
    )
    (net (code "39") (name "Net-(ADR1-Pad3)") (class "Default")
      (node (ref "ADR1") (pin "3") (pinfunction "3_3") (pintype "passive"))
      (node (ref "RADR1A") (pin "1") (pinfunction "1_1") (pintype "passive"))
    )
    (net (code "40") (name "Net-(IC1A-CLK)") (class "Default")
      (node (ref "C8") (pin "1") (pinfunction "1_1") (pintype "passive"))
      (node (ref "IC1") (pin "12") (pinfunction "D_12") (pintype "input"))
      (node (ref "IC1") (pin "13") (pinfunction "CLR_13") (pintype "input"))
      (node (ref "IC1") (pin "3") (pinfunction "CLK_3") (pintype "input"))
      (node (ref "R_ENC2") (pin "1") (pinfunction "1_1") (pintype "passive"))
    )
    (net (code "41") (name "Net-(IC1A-CLR)") (class "Default")
      (node (ref "C7") (pin "1") (pinfunction "1_1") (pintype "passive"))
      (node (ref "IC1") (pin "1") (pinfunction "CLR_1") (pintype "input"))
      (node (ref "IC1") (pin "11") (pinfunction "CLK_11") (pintype "input"))
      (node (ref "IC1") (pin "2") (pinfunction "D_2") (pintype "input"))
      (node (ref "R_ENC1") (pin "1") (pinfunction "1_1") (pintype "passive"))
    )
    (net (code "42") (name "Net-(IC2A-CLK)") (class "Default")
      (node (ref "C14") (pin "1") (pinfunction "1_1") (pintype "passive"))
      (node (ref "IC2") (pin "12") (pinfunction "D_12") (pintype "input"))
      (node (ref "IC2") (pin "13") (pinfunction "CLR_13") (pintype "input"))
      (node (ref "IC2") (pin "3") (pinfunction "CLK_3") (pintype "input"))
      (node (ref "R_ENC12") (pin "1") (pinfunction "1_1") (pintype "passive"))
    )
    (net (code "43") (name "Net-(IC2A-CLR)") (class "Default")
      (node (ref "C13") (pin "1") (pinfunction "1_1") (pintype "passive"))
      (node (ref "IC2") (pin "1") (pinfunction "CLR_1") (pintype "input"))
      (node (ref "IC2") (pin "11") (pinfunction "CLK_11") (pintype "input"))
      (node (ref "IC2") (pin "2") (pinfunction "D_2") (pintype "input"))
      (node (ref "R_ENC11") (pin "1") (pinfunction "1_1") (pintype "passive"))
    )
    (net (code "44") (name "Net-(IC3A-CLK)") (class "Default")
      (node (ref "C10") (pin "1") (pinfunction "1_1") (pintype "passive"))
      (node (ref "IC3") (pin "12") (pinfunction "D_12") (pintype "input"))
      (node (ref "IC3") (pin "13") (pinfunction "CLR_13") (pintype "input"))
      (node (ref "IC3") (pin "3") (pinfunction "CLK_3") (pintype "input"))
      (node (ref "R_ENC4") (pin "1") (pinfunction "1_1") (pintype "passive"))
    )
    (net (code "45") (name "Net-(IC3A-CLR)") (class "Default")
      (node (ref "C9") (pin "1") (pinfunction "1_1") (pintype "passive"))
      (node (ref "IC3") (pin "1") (pinfunction "CLR_1") (pintype "input"))
      (node (ref "IC3") (pin "11") (pinfunction "CLK_11") (pintype "input"))
      (node (ref "IC3") (pin "2") (pinfunction "D_2") (pintype "input"))
      (node (ref "R_ENC3") (pin "1") (pinfunction "1_1") (pintype "passive"))
    )
    (net (code "46") (name "Net-(IC4A-CLK)") (class "Default")
      (node (ref "C12") (pin "1") (pinfunction "1_1") (pintype "passive"))
      (node (ref "IC4") (pin "12") (pinfunction "D_12") (pintype "input"))
      (node (ref "IC4") (pin "13") (pinfunction "CLR_13") (pintype "input"))
      (node (ref "IC4") (pin "3") (pinfunction "CLK_3") (pintype "input"))
      (node (ref "R_ENC6") (pin "1") (pinfunction "1_1") (pintype "passive"))
    )
    (net (code "47") (name "Net-(IC4A-CLR)") (class "Default")
      (node (ref "C11") (pin "1") (pinfunction "1_1") (pintype "passive"))
      (node (ref "IC4") (pin "1") (pinfunction "CLR_1") (pintype "input"))
      (node (ref "IC4") (pin "11") (pinfunction "CLK_11") (pintype "input"))
      (node (ref "IC4") (pin "2") (pinfunction "D_2") (pintype "input"))
      (node (ref "R_ENC5") (pin "1") (pinfunction "1_1") (pintype "passive"))
    )
    (net (code "48") (name "Net-(JP1-RXI)") (class "Default")
      (node (ref "JP1") (pin "P$3") (pinfunction "RXI_P$3") (pintype "bidirectional"))
      (node (ref "R1") (pin "1") (pinfunction "1_1") (pintype "passive"))
    )
    (net (code "49") (name "Net-(JP1-TXO)") (class "Default")
      (node (ref "JP1") (pin "P$2") (pinfunction "TXO_P$2") (pintype "bidirectional"))
      (node (ref "R2") (pin "1") (pinfunction "1_1") (pintype "passive"))
    )
    (net (code "50") (name "Net-(JP1-VCC)") (class "Default")
      (node (ref "JP1") (pin "P$4") (pinfunction "VCC_P$4") (pintype "bidirectional"))
      (node (ref "JP5") (pin "1") (pinfunction "1_1") (pintype "passive"))
    )
    (net (code "51") (name "Net-(POWERLED-PadC)") (class "Default")
      (node (ref "POWERLED") (pin "C") (pinfunction "C_C") (pintype "passive"))
      (node (ref "R4") (pin "2") (pinfunction "2_2") (pintype "passive"))
    )
    (net (code "52") (name "Net-(U$1-BYPASS)") (class "Default")
      (node (ref "C2") (pin "1") (pinfunction "1_1") (pintype "passive"))
      (node (ref "U$1") (pin "4") (pinfunction "BYPASS_4") (pintype "bidirectional"))
    )
    (net (code "53") (name "Net-(U$6-VOUT)") (class "Default")
      (node (ref "ROUT") (pin "1") (pinfunction "1_1") (pintype "passive"))
      (node (ref "U$6") (pin "8") (pinfunction "VOUT_8") (pintype "bidirectional"))
    )
    (net (code "54") (name "Net-(U1-PB6(XTAL1{slash}TOSC1))") (class "Default")
      (node (ref "U1") (pin "7") (pinfunction "PB6(XTAL1/TOSC1)_7") (pintype "bidirectional"))
      (node (ref "Y1") (pin "1") (pinfunction "1_1") (pintype "passive"))
    )
    (net (code "55") (name "Net-(U1-PB7(XTAL2{slash}TOSC2))") (class "Default")
      (node (ref "U1") (pin "8") (pinfunction "PB7(XTAL2/TOSC2)_8") (pintype "bidirectional"))
      (node (ref "Y1") (pin "3") (pinfunction "3_3") (pintype "passive"))
    )
    (net (code "56") (name "Net-(VREG-VI)") (class "Default")
      (node (ref "C21") (pin "+") (pinfunction "+_+") (pintype "passive"))
      (node (ref "C33") (pin "1") (pinfunction "1_1") (pintype "passive"))
      (node (ref "C34") (pin "1") (pinfunction "1_1") (pintype "passive"))
      (node (ref "D1") (pin "C") (pinfunction "C_C") (pintype "passive"))
      (node (ref "L1") (pin "2") (pinfunction "2_2") (pintype "passive"))
      (node (ref "VREG") (pin "1") (pinfunction "VI_1") (pintype "input"))
    )
    (net (code "57") (name "Net-(X1A-K)") (class "Default")
      (node (ref "DRIVER1") (pin "VOUT-") (pinfunction "VOUT-_VOUT-") (pintype "bidirectional"))
      (node (ref "X1") (pin "1") (pinfunction "K_1") (pintype "passive"))
    )
    (net (code "58") (name "Net-(X1B-K)") (class "Default")
      (node (ref "DRIVER1") (pin "VOUT+") (pinfunction "VOUT+_VOUT+") (pintype "bidirectional"))
      (node (ref "X1") (pin "2") (pinfunction "K_2") (pintype "passive"))
    )
    (net (code "59") (name "RST") (class "Default")
      (node (ref "C_RST") (pin "1") (pinfunction "1_1") (pintype "passive"))
      (node (ref "J1") (pin "5") (pinfunction "5_5") (pintype "passive"))
      (node (ref "R3") (pin "2") (pinfunction "2_2") (pintype "passive"))
      (node (ref "S1") (pin "3") (pinfunction "3_3") (pintype "passive"))
      (node (ref "S1") (pin "4") (pinfunction "4_4") (pintype "passive"))
      (node (ref "U1") (pin "29") (pinfunction "PC6(/RESET)_29") (pintype "bidirectional"))
    )
    (net (code "60") (name "RX") (class "Default")
      (node (ref "R1") (pin "2") (pinfunction "2_2") (pintype "passive"))
      (node (ref "U1") (pin "30") (pinfunction "PD0(RXD)_30") (pintype "bidirectional"))
    )
    (net (code "61") (name "SCK") (class "Default")
      (node (ref "J1") (pin "3") (pinfunction "3_3") (pintype "passive"))
      (node (ref "U1") (pin "17") (pinfunction "PB5(SCK)_17") (pintype "bidirectional"))
    )
    (net (code "62") (name "SCL") (class "Default")
      (node (ref "EMOVE") (pin "1") (pinfunction "1_1") (pintype "passive"))
      (node (ref "JP4") (pin "9") (pinfunction "9_9") (pintype "passive"))
      (node (ref "Q2") (pin "2") (pinfunction "S_2") (pintype "passive"))
      (node (ref "U$6") (pin "3") (pinfunction "SCL_3") (pintype "bidirectional"))
    )
    (net (code "63") (name "SCL_5V") (class "Default")
      (node (ref "Q2") (pin "3") (pinfunction "D_3") (pintype "passive"))
      (node (ref "R7") (pin "1") (pinfunction "1_1") (pintype "passive"))
      (node (ref "U1") (pin "28") (pinfunction "PC5(ADC5/SCL)_28") (pintype "bidirectional"))
    )
    (net (code "64") (name "SDA") (class "Default")
      (node (ref "JP4") (pin "10") (pinfunction "10_10") (pintype "passive"))
      (node (ref "Q1") (pin "2") (pinfunction "S_2") (pintype "passive"))
      (node (ref "R6") (pin "1") (pinfunction "1_1") (pintype "passive"))
      (node (ref "U$6") (pin "4") (pinfunction "SDA_4") (pintype "bidirectional"))
    )
    (net (code "65") (name "SDA_5V") (class "Default")
      (node (ref "Q1") (pin "3") (pinfunction "D_3") (pintype "passive"))
      (node (ref "R5") (pin "1") (pinfunction "1_1") (pintype "passive"))
      (node (ref "U1") (pin "27") (pinfunction "PC4(ADC4/SDA)_27") (pintype "bidirectional"))
    )
    (net (code "66") (name "TX") (class "Default")
      (node (ref "R2") (pin "2") (pinfunction "2_2") (pintype "passive"))
      (node (ref "U1") (pin "31") (pinfunction "PD1(TXD)_31") (pintype "bidirectional"))
    )
    (net (code "67") (name "VIN+") (class "Default")
      (node (ref "C29") (pin "+") (pinfunction "+_+") (pintype "passive"))
      (node (ref "C30") (pin "+") (pinfunction "+_+") (pintype "passive"))
      (node (ref "C31") (pin "1") (pinfunction "1_1") (pintype "passive"))
      (node (ref "C32") (pin "1") (pinfunction "1_1") (pintype "passive"))
      (node (ref "DRIVER1") (pin "VIN+") (pinfunction "VIN+_VIN+") (pintype "bidirectional"))
      (node (ref "L1") (pin "1") (pinfunction "1_1") (pintype "passive"))
      (node (ref "POWERLED") (pin "A") (pinfunction "A_A") (pintype "passive"))
      (node (ref "X2") (pin "2") (pinfunction "K_2") (pintype "passive"))
    )
    (net (code "68") (name "VIN-") (class "Default")
      (node (ref "C29") (pin "-") (pinfunction "-_-") (pintype "passive"))
      (node (ref "C30") (pin "-") (pinfunction "-_-") (pintype "passive"))
      (node (ref "C31") (pin "2") (pinfunction "2_2") (pintype "passive"))
      (node (ref "C32") (pin "2") (pinfunction "2_2") (pintype "passive"))
      (node (ref "DRIVER1") (pin "VIN-") (pinfunction "VIN-_VIN-") (pintype "bidirectional"))
      (node (ref "GND_JP") (pin "1") (pinfunction "1_1") (pintype "passive"))
      (node (ref "X2") (pin "1") (pinfunction "K_1") (pintype "passive"))
    )
    (net (code "69") (name "VOUT") (class "Default")
      (node (ref "DRIVER1") (pin "ANALOGDIM") (pinfunction "ANALOGDIM_ANALOGDIM") (pintype "bidirectional"))
      (node (ref "ROUT") (pin "2") (pinfunction "2_2") (pintype "passive"))
    )
    (net (code "70") (name "unconnected-(DRIVER1-PadDIM-)") (class "Default")
      (node (ref "DRIVER1") (pin "DIM-") (pinfunction "DIM-_DIM-") (pintype "bidirectional"))
    )
    (net (code "71") (name "unconnected-(DRIVER1-PadPWMDIM)") (class "Default")
      (node (ref "DRIVER1") (pin "PWMDIM") (pinfunction "PWMDIM_PWMDIM") (pintype "bidirectional"))
    )
    (net (code "72") (name "unconnected-(IC1A-PRE-Pad4)") (class "Default")
      (node (ref "IC1") (pin "4") (pinfunction "PRE_4") (pintype "input"))
    )
    (net (code "73") (name "unconnected-(IC1A-~{Q}-Pad6)") (class "Default")
      (node (ref "IC1") (pin "6") (pinfunction "~{Q}_6") (pintype "output"))
    )
    (net (code "74") (name "unconnected-(IC1B-PRE-Pad10)") (class "Default")
      (node (ref "IC1") (pin "10") (pinfunction "PRE_10") (pintype "input"))
    )
    (net (code "75") (name "unconnected-(IC1B-~{Q}-Pad8)") (class "Default")
      (node (ref "IC1") (pin "8") (pinfunction "~{Q}_8") (pintype "output"))
    )
    (net (code "76") (name "unconnected-(IC2A-PRE-Pad4)") (class "Default")
      (node (ref "IC2") (pin "4") (pinfunction "PRE_4") (pintype "input"))
    )
    (net (code "77") (name "unconnected-(IC2A-~{Q}-Pad6)") (class "Default")
      (node (ref "IC2") (pin "6") (pinfunction "~{Q}_6") (pintype "output"))
    )
    (net (code "78") (name "unconnected-(IC2B-PRE-Pad10)") (class "Default")
      (node (ref "IC2") (pin "10") (pinfunction "PRE_10") (pintype "input"))
    )
    (net (code "79") (name "unconnected-(IC2B-~{Q}-Pad8)") (class "Default")
      (node (ref "IC2") (pin "8") (pinfunction "~{Q}_8") (pintype "output"))
    )
    (net (code "80") (name "unconnected-(IC3A-PRE-Pad4)") (class "Default")
      (node (ref "IC3") (pin "4") (pinfunction "PRE_4") (pintype "input"))
    )
    (net (code "81") (name "unconnected-(IC3A-~{Q}-Pad6)") (class "Default")
      (node (ref "IC3") (pin "6") (pinfunction "~{Q}_6") (pintype "output"))
    )
    (net (code "82") (name "unconnected-(IC3B-PRE-Pad10)") (class "Default")
      (node (ref "IC3") (pin "10") (pinfunction "PRE_10") (pintype "input"))
    )
    (net (code "83") (name "unconnected-(IC3B-~{Q}-Pad8)") (class "Default")
      (node (ref "IC3") (pin "8") (pinfunction "~{Q}_8") (pintype "output"))
    )
    (net (code "84") (name "unconnected-(IC4A-PRE-Pad4)") (class "Default")
      (node (ref "IC4") (pin "4") (pinfunction "PRE_4") (pintype "input"))
    )
    (net (code "85") (name "unconnected-(IC4A-~{Q}-Pad6)") (class "Default")
      (node (ref "IC4") (pin "6") (pinfunction "~{Q}_6") (pintype "output"))
    )
    (net (code "86") (name "unconnected-(IC4B-PRE-Pad10)") (class "Default")
      (node (ref "IC4") (pin "10") (pinfunction "PRE_10") (pintype "input"))
    )
    (net (code "87") (name "unconnected-(IC4B-~{Q}-Pad8)") (class "Default")
      (node (ref "IC4") (pin "8") (pinfunction "~{Q}_8") (pintype "output"))
    )
    (net (code "88") (name "unconnected-(JP1-CTS-PadP$5)") (class "Default")
      (node (ref "JP1") (pin "P$5") (pinfunction "CTS_P$5") (pintype "bidirectional"))
    )
    (net (code "89") (name "unconnected-(JP4-Pad7)") (class "Default")
      (node (ref "JP4") (pin "7") (pinfunction "7_7") (pintype "passive"))
    )
    (net (code "90") (name "unconnected-(JP4-Pad8)") (class "Default")
      (node (ref "JP4") (pin "8") (pinfunction "8_8") (pintype "passive"))
    )
    (net (code "91") (name "unconnected-(U1-ADC6-Pad19)") (class "Default")
      (node (ref "U1") (pin "19") (pinfunction "ADC6_19") (pintype "bidirectional"))
    )
    (net (code "92") (name "unconnected-(U1-ADC7-Pad22)") (class "Default")
      (node (ref "U1") (pin "22") (pinfunction "ADC7_22") (pintype "bidirectional"))
    )
  )
)
